# MPC.net
KiCad netlist of a schematic drawn in Altium Designer
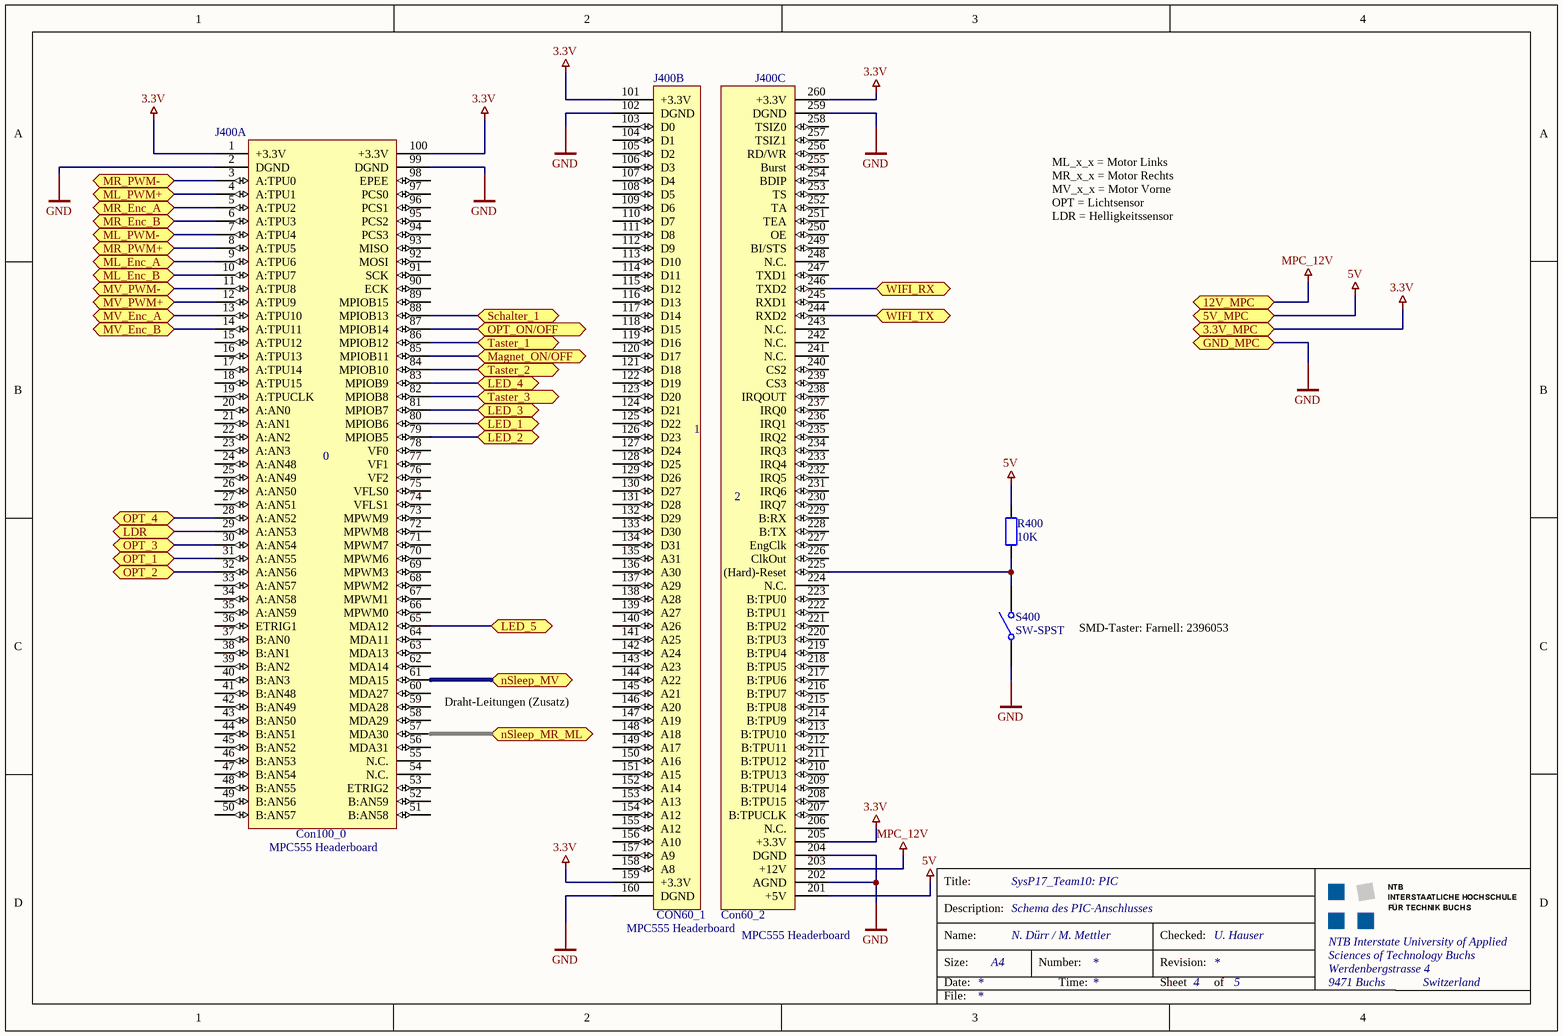
[diagram p0: MPC.SchDoc]

(export (version "E")
  (design (tool "Eeschema 10.0.6"))
  (components
    (comp (ref "J400")
      (value "MPC555 Headerboard")
      (footprint "MPC555 Headerboard THT")
      (description "NTB MPC555 Headerboard")
      (libsource (lib "ch.ntb.inf.altiumlib_2011-02-10") (part "MPC555 Headerboard"))
    )
    (comp (ref "R400")
      (value "10K")
      (footprint "GEN_R0805_H")
      (description "generic resistor")
      (fields
        (field (name "MANUFACTURER") "Tbd")
        (field (name "Comment") "Generic")
        (field (name "PUBLISHER") "Altium Limited")
      )
      (libsource (lib "Motortreiber") (part "GEN_R_2"))
    )
    (comp (ref "S400")
      (value "SW-SPST")
      (footprint "Taster")
      (description "Single-Pole, Single-Throw Switch")
      (fields (field (name "PUBLISHER") "Altium Limited"))
      (libsource (lib "Miscellaneous Devices") (part "SW-SPST"))
    )
  )
  (nets
    (net (code "1") (name "/LDR") (class "Default")
      (node (ref "J400") (pin "29") (pinfunction "A:AN53_29") (pintype "bidirectional"))
    )
    (net (code "2") (name "/LED_1") (class "Default")
      (node (ref "J400") (pin "80") (pinfunction "MPIOB6_80") (pintype "bidirectional"))
    )
    (net (code "3") (name "/LED_2") (class "Default")
      (node (ref "J400") (pin "79") (pinfunction "MPIOB5_79") (pintype "bidirectional"))
    )
    (net (code "4") (name "/LED_3") (class "Default")
      (node (ref "J400") (pin "81") (pinfunction "MPIOB7_81") (pintype "bidirectional"))
    )
    (net (code "5") (name "/LED_4") (class "Default")
      (node (ref "J400") (pin "83") (pinfunction "MPIOB9_83") (pintype "bidirectional"))
    )
    (net (code "6") (name "/LED_5") (class "Default")
      (node (ref "J400") (pin "65") (pinfunction "MDA12_65") (pintype "bidirectional"))
    )
    (net (code "7") (name "/ML_Enc_A") (class "Default")
      (node (ref "J400") (pin "9") (pinfunction "A:TPU6_9") (pintype "bidirectional"))
    )
    (net (code "8") (name "/ML_Enc_B") (class "Default")
      (node (ref "J400") (pin "10") (pinfunction "A:TPU7_10") (pintype "bidirectional"))
    )
    (net (code "9") (name "/ML_PWM+") (class "Default")
      (node (ref "J400") (pin "4") (pinfunction "A:TPU1_4") (pintype "bidirectional"))
    )
    (net (code "10") (name "/ML_PWM-") (class "Default")
      (node (ref "J400") (pin "7") (pinfunction "A:TPU4_7") (pintype "bidirectional"))
    )
    (net (code "11") (name "/MR_Enc_A") (class "Default")
      (node (ref "J400") (pin "5") (pinfunction "A:TPU2_5") (pintype "bidirectional"))
    )
    (net (code "12") (name "/MR_Enc_B") (class "Default")
      (node (ref "J400") (pin "6") (pinfunction "A:TPU3_6") (pintype "bidirectional"))
    )
    (net (code "13") (name "/MR_PWM+") (class "Default")
      (node (ref "J400") (pin "8") (pinfunction "A:TPU5_8") (pintype "bidirectional"))
    )
    (net (code "14") (name "/MR_PWM-") (class "Default")
      (node (ref "J400") (pin "3") (pinfunction "A:TPU0_3") (pintype "bidirectional"))
    )
    (net (code "15") (name "/MV_Enc_A") (class "Default")
      (node (ref "J400") (pin "13") (pinfunction "A:TPU10_13") (pintype "bidirectional"))
    )
    (net (code "16") (name "/MV_Enc_B") (class "Default")
      (node (ref "J400") (pin "14") (pinfunction "A:TPU11_14") (pintype "bidirectional"))
    )
    (net (code "17") (name "/MV_PWM+") (class "Default")
      (node (ref "J400") (pin "12") (pinfunction "A:TPU9_12") (pintype "bidirectional"))
    )
    (net (code "18") (name "/MV_PWM-") (class "Default")
      (node (ref "J400") (pin "11") (pinfunction "A:TPU8_11") (pintype "bidirectional"))
    )
    (net (code "19") (name "/Magnet_ON{slash}OFF") (class "Default")
      (node (ref "J400") (pin "85") (pinfunction "MPIOB11_85") (pintype "bidirectional"))
    )
    (net (code "20") (name "/OPT_1") (class "Default")
      (node (ref "J400") (pin "31") (pinfunction "A:AN55_31") (pintype "bidirectional"))
    )
    (net (code "21") (name "/OPT_2") (class "Default")
      (node (ref "J400") (pin "32") (pinfunction "A:AN56_32") (pintype "bidirectional"))
    )
    (net (code "22") (name "/OPT_3") (class "Default")
      (node (ref "J400") (pin "30") (pinfunction "A:AN54_30") (pintype "bidirectional"))
    )
    (net (code "23") (name "/OPT_4") (class "Default")
      (node (ref "J400") (pin "28") (pinfunction "A:AN52_28") (pintype "bidirectional"))
    )
    (net (code "24") (name "/OPT_ON{slash}OFF") (class "Default")
      (node (ref "J400") (pin "87") (pinfunction "MPIOB14_87") (pintype "bidirectional"))
    )
    (net (code "25") (name "/Schalter_1") (class "Default")
      (node (ref "J400") (pin "88") (pinfunction "MPIOB13_88") (pintype "bidirectional"))
    )
    (net (code "26") (name "/Taster_1") (class "Default")
      (node (ref "J400") (pin "86") (pinfunction "MPIOB12_86") (pintype "bidirectional"))
    )
    (net (code "27") (name "/Taster_2") (class "Default")
      (node (ref "J400") (pin "84") (pinfunction "MPIOB10_84") (pintype "bidirectional"))
    )
    (net (code "28") (name "/Taster_3") (class "Default")
      (node (ref "J400") (pin "82") (pinfunction "MPIOB8_82") (pintype "bidirectional"))
    )
    (net (code "29") (name "/WIFI_RX") (class "Default")
      (node (ref "J400") (pin "246") (pinfunction "TXD2_246") (pintype "bidirectional"))
    )
    (net (code "30") (name "/WIFI_TX") (class "Default")
      (node (ref "J400") (pin "244") (pinfunction "RXD2_244") (pintype "bidirectional"))
    )
    (net (code "31") (name "/nSleep_MR_ML") (class "Default")
      (node (ref "J400") (pin "57") (pinfunction "MDA30_57") (pintype "bidirectional"))
    )
    (net (code "32") (name "/nSleep_MV") (class "Default")
      (node (ref "J400") (pin "61") (pinfunction "MDA15_61") (pintype "bidirectional"))
    )
    (net (code "33") (name "3.3V") (class "Default")
      (node (ref "J400") (pin "1") (pinfunction "+3.3V_1") (pintype "power_in"))
      (node (ref "J400") (pin "100") (pinfunction "+3.3V_100") (pintype "power_in"))
      (node (ref "J400") (pin "101") (pinfunction "+3.3V_101") (pintype "power_in"))
      (node (ref "J400") (pin "159") (pinfunction "+3.3V_159") (pintype "power_in"))
      (node (ref "J400") (pin "205") (pinfunction "+3.3V_205") (pintype "power_in"))
      (node (ref "J400") (pin "260") (pinfunction "+3.3V_260") (pintype "power_in"))
    )
    (net (code "34") (name "5V") (class "Default")
      (node (ref "J400") (pin "201") (pinfunction "+5V_201") (pintype "power_in"))
      (node (ref "R400") (pin "2") (pinfunction "2_2") (pintype "passive"))
    )
    (net (code "35") (name "GND") (class "Default")
      (node (ref "J400") (pin "102") (pinfunction "DGND_102") (pintype "power_in"))
      (node (ref "J400") (pin "160") (pinfunction "DGND_160") (pintype "power_in"))
      (node (ref "J400") (pin "2") (pinfunction "DGND_2") (pintype "power_in"))
      (node (ref "J400") (pin "202") (pinfunction "AGND_202") (pintype "power_in"))
      (node (ref "J400") (pin "204") (pinfunction "DGND_204") (pintype "power_in"))
      (node (ref "J400") (pin "259") (pinfunction "DGND_259") (pintype "power_in"))
      (node (ref "J400") (pin "99") (pinfunction "DGND_99") (pintype "power_in"))
      (node (ref "S400") (pin "1") (pinfunction "COMMON_1") (pintype "passive"))
    )
    (net (code "36") (name "MPC_12V") (class "Default")
      (node (ref "J400") (pin "203") (pinfunction "+12V_203") (pintype "power_in"))
    )
    (net (code "37") (name "Net-(J400C-(Hard)-Reset)") (class "Default")
      (node (ref "J400") (pin "225") (pinfunction "(Hard)-Reset_225") (pintype "bidirectional"))
      (node (ref "R400") (pin "1") (pinfunction "1_1") (pintype "passive"))
      (node (ref "S400") (pin "0") (pinfunction "NO_0") (pintype "passive"))
    )
    (net (code "38") (name "unconnected-(J400A-A:AN0-Pad20)") (class "Default")
      (node (ref "J400") (pin "20") (pinfunction "A:AN0_20") (pintype "bidirectional"))
    )
    (net (code "39") (name "unconnected-(J400A-A:AN1-Pad21)") (class "Default")
      (node (ref "J400") (pin "21") (pinfunction "A:AN1_21") (pintype "bidirectional"))
    )
    (net (code "40") (name "unconnected-(J400A-A:AN2-Pad22)") (class "Default")
      (node (ref "J400") (pin "22") (pinfunction "A:AN2_22") (pintype "bidirectional"))
    )
    (net (code "41") (name "unconnected-(J400A-A:AN3-Pad23)") (class "Default")
      (node (ref "J400") (pin "23") (pinfunction "A:AN3_23") (pintype "bidirectional"))
    )
    (net (code "42") (name "unconnected-(J400A-A:AN48-Pad24)") (class "Default")
      (node (ref "J400") (pin "24") (pinfunction "A:AN48_24") (pintype "bidirectional"))
    )
    (net (code "43") (name "unconnected-(J400A-A:AN49-Pad25)") (class "Default")
      (node (ref "J400") (pin "25") (pinfunction "A:AN49_25") (pintype "bidirectional"))
    )
    (net (code "44") (name "unconnected-(J400A-A:AN50-Pad26)") (class "Default")
      (node (ref "J400") (pin "26") (pinfunction "A:AN50_26") (pintype "bidirectional"))
    )
    (net (code "45") (name "unconnected-(J400A-A:AN51-Pad27)") (class "Default")
      (node (ref "J400") (pin "27") (pinfunction "A:AN51_27") (pintype "bidirectional"))
    )
    (net (code "46") (name "unconnected-(J400A-A:AN57-Pad33)") (class "Default")
      (node (ref "J400") (pin "33") (pinfunction "A:AN57_33") (pintype "bidirectional"))
    )
    (net (code "47") (name "unconnected-(J400A-A:AN58-Pad34)") (class "Default")
      (node (ref "J400") (pin "34") (pinfunction "A:AN58_34") (pintype "bidirectional"))
    )
    (net (code "48") (name "unconnected-(J400A-A:AN59-Pad35)") (class "Default")
      (node (ref "J400") (pin "35") (pinfunction "A:AN59_35") (pintype "bidirectional"))
    )
    (net (code "49") (name "unconnected-(J400A-A:TPU12-Pad15)") (class "Default")
      (node (ref "J400") (pin "15") (pinfunction "A:TPU12_15") (pintype "bidirectional"))
    )
    (net (code "50") (name "unconnected-(J400A-A:TPU13-Pad16)") (class "Default")
      (node (ref "J400") (pin "16") (pinfunction "A:TPU13_16") (pintype "bidirectional"))
    )
    (net (code "51") (name "unconnected-(J400A-A:TPU14-Pad17)") (class "Default")
      (node (ref "J400") (pin "17") (pinfunction "A:TPU14_17") (pintype "bidirectional"))
    )
    (net (code "52") (name "unconnected-(J400A-A:TPU15-Pad18)") (class "Default")
      (node (ref "J400") (pin "18") (pinfunction "A:TPU15_18") (pintype "bidirectional"))
    )
    (net (code "53") (name "unconnected-(J400A-A:TPUCLK-Pad19)") (class "Default")
      (node (ref "J400") (pin "19") (pinfunction "A:TPUCLK_19") (pintype "bidirectional"))
    )
    (net (code "54") (name "unconnected-(J400A-B:AN0-Pad37)") (class "Default")
      (node (ref "J400") (pin "37") (pinfunction "B:AN0_37") (pintype "bidirectional"))
    )
    (net (code "55") (name "unconnected-(J400A-B:AN1-Pad38)") (class "Default")
      (node (ref "J400") (pin "38") (pinfunction "B:AN1_38") (pintype "bidirectional"))
    )
    (net (code "56") (name "unconnected-(J400A-B:AN2-Pad39)") (class "Default")
      (node (ref "J400") (pin "39") (pinfunction "B:AN2_39") (pintype "bidirectional"))
    )
    (net (code "57") (name "unconnected-(J400A-B:AN3-Pad40)") (class "Default")
      (node (ref "J400") (pin "40") (pinfunction "B:AN3_40") (pintype "bidirectional"))
    )
    (net (code "58") (name "unconnected-(J400A-B:AN48-Pad41)") (class "Default")
      (node (ref "J400") (pin "41") (pinfunction "B:AN48_41") (pintype "bidirectional"))
    )
    (net (code "59") (name "unconnected-(J400A-B:AN49-Pad42)") (class "Default")
      (node (ref "J400") (pin "42") (pinfunction "B:AN49_42") (pintype "bidirectional"))
    )
    (net (code "60") (name "unconnected-(J400A-B:AN50-Pad43)") (class "Default")
      (node (ref "J400") (pin "43") (pinfunction "B:AN50_43") (pintype "bidirectional"))
    )
    (net (code "61") (name "unconnected-(J400A-B:AN51-Pad44)") (class "Default")
      (node (ref "J400") (pin "44") (pinfunction "B:AN51_44") (pintype "bidirectional"))
    )
    (net (code "62") (name "unconnected-(J400A-B:AN52-Pad45)") (class "Default")
      (node (ref "J400") (pin "45") (pinfunction "B:AN52_45") (pintype "bidirectional"))
    )
    (net (code "63") (name "unconnected-(J400A-B:AN53-Pad46)") (class "Default")
      (node (ref "J400") (pin "46") (pinfunction "B:AN53_46") (pintype "bidirectional"))
    )
    (net (code "64") (name "unconnected-(J400A-B:AN54-Pad47)") (class "Default")
      (node (ref "J400") (pin "47") (pinfunction "B:AN54_47") (pintype "bidirectional"))
    )
    (net (code "65") (name "unconnected-(J400A-B:AN55-Pad48)") (class "Default")
      (node (ref "J400") (pin "48") (pinfunction "B:AN55_48") (pintype "bidirectional"))
    )
    (net (code "66") (name "unconnected-(J400A-B:AN56-Pad49)") (class "Default")
      (node (ref "J400") (pin "49") (pinfunction "B:AN56_49") (pintype "bidirectional"))
    )
    (net (code "67") (name "unconnected-(J400A-B:AN57-Pad50)") (class "Default")
      (node (ref "J400") (pin "50") (pinfunction "B:AN57_50") (pintype "bidirectional"))
    )
    (net (code "68") (name "unconnected-(J400A-B:AN58-Pad51)") (class "Default")
      (node (ref "J400") (pin "51") (pinfunction "B:AN58_51") (pintype "bidirectional"))
    )
    (net (code "69") (name "unconnected-(J400A-B:AN59-Pad52)") (class "Default")
      (node (ref "J400") (pin "52") (pinfunction "B:AN59_52") (pintype "bidirectional"))
    )
    (net (code "70") (name "unconnected-(J400A-ECK-Pad90)") (class "Default")
      (node (ref "J400") (pin "90") (pinfunction "ECK_90") (pintype "bidirectional"))
    )
    (net (code "71") (name "unconnected-(J400A-EPEE-Pad98)") (class "Default")
      (node (ref "J400") (pin "98") (pinfunction "EPEE_98") (pintype "bidirectional"))
    )
    (net (code "72") (name "unconnected-(J400A-ETRIG1-Pad36)") (class "Default")
      (node (ref "J400") (pin "36") (pinfunction "ETRIG1_36") (pintype "bidirectional"))
    )
    (net (code "73") (name "unconnected-(J400A-ETRIG2-Pad53)") (class "Default")
      (node (ref "J400") (pin "53") (pinfunction "ETRIG2_53") (pintype "bidirectional"))
    )
    (net (code "74") (name "unconnected-(J400A-MDA11-Pad64)") (class "Default")
      (node (ref "J400") (pin "64") (pinfunction "MDA11_64") (pintype "bidirectional"))
    )
    (net (code "75") (name "unconnected-(J400A-MDA13-Pad63)") (class "Default")
      (node (ref "J400") (pin "63") (pinfunction "MDA13_63") (pintype "bidirectional"))
    )
    (net (code "76") (name "unconnected-(J400A-MDA14-Pad62)") (class "Default")
      (node (ref "J400") (pin "62") (pinfunction "MDA14_62") (pintype "bidirectional"))
    )
    (net (code "77") (name "unconnected-(J400A-MDA27-Pad60)") (class "Default")
      (node (ref "J400") (pin "60") (pinfunction "MDA27_60") (pintype "bidirectional"))
    )
    (net (code "78") (name "unconnected-(J400A-MDA28-Pad59)") (class "Default")
      (node (ref "J400") (pin "59") (pinfunction "MDA28_59") (pintype "bidirectional"))
    )
    (net (code "79") (name "unconnected-(J400A-MDA29-Pad58)") (class "Default")
      (node (ref "J400") (pin "58") (pinfunction "MDA29_58") (pintype "bidirectional"))
    )
    (net (code "80") (name "unconnected-(J400A-MDA31-Pad56)") (class "Default")
      (node (ref "J400") (pin "56") (pinfunction "MDA31_56") (pintype "bidirectional"))
    )
    (net (code "81") (name "unconnected-(J400A-MISO-Pad93)") (class "Default")
      (node (ref "J400") (pin "93") (pinfunction "MISO_93") (pintype "bidirectional"))
    )
    (net (code "82") (name "unconnected-(J400A-MOSI-Pad92)") (class "Default")
      (node (ref "J400") (pin "92") (pinfunction "MOSI_92") (pintype "bidirectional"))
    )
    (net (code "83") (name "unconnected-(J400A-MPIOB15-Pad89)") (class "Default")
      (node (ref "J400") (pin "89") (pinfunction "MPIOB15_89") (pintype "bidirectional"))
    )
    (net (code "84") (name "unconnected-(J400A-MPWM0-Pad66)") (class "Default")
      (node (ref "J400") (pin "66") (pinfunction "MPWM0_66") (pintype "bidirectional"))
    )
    (net (code "85") (name "unconnected-(J400A-MPWM1-Pad67)") (class "Default")
      (node (ref "J400") (pin "67") (pinfunction "MPWM1_67") (pintype "bidirectional"))
    )
    (net (code "86") (name "unconnected-(J400A-MPWM2-Pad68)") (class "Default")
      (node (ref "J400") (pin "68") (pinfunction "MPWM2_68") (pintype "bidirectional"))
    )
    (net (code "87") (name "unconnected-(J400A-MPWM3-Pad69)") (class "Default")
      (node (ref "J400") (pin "69") (pinfunction "MPWM3_69") (pintype "bidirectional"))
    )
    (net (code "88") (name "unconnected-(J400A-MPWM6-Pad70)") (class "Default")
      (node (ref "J400") (pin "70") (pinfunction "MPWM6_70") (pintype "bidirectional"))
    )
    (net (code "89") (name "unconnected-(J400A-MPWM7-Pad71)") (class "Default")
      (node (ref "J400") (pin "71") (pinfunction "MPWM7_71") (pintype "bidirectional"))
    )
    (net (code "90") (name "unconnected-(J400A-MPWM8-Pad72)") (class "Default")
      (node (ref "J400") (pin "72") (pinfunction "MPWM8_72") (pintype "bidirectional"))
    )
    (net (code "91") (name "unconnected-(J400A-MPWM9-Pad73)") (class "Default")
      (node (ref "J400") (pin "73") (pinfunction "MPWM9_73") (pintype "bidirectional"))
    )
    (net (code "92") (name "unconnected-(J400A-N.C.-Pad54)") (class "Default")
      (node (ref "J400") (pin "54") (pinfunction "N.C._54") (pintype "tri_state"))
    )
    (net (code "93") (name "unconnected-(J400A-N.C.-Pad55)") (class "Default")
      (node (ref "J400") (pin "55") (pinfunction "N.C._55") (pintype "tri_state"))
    )
    (net (code "94") (name "unconnected-(J400A-PCS0-Pad97)") (class "Default")
      (node (ref "J400") (pin "97") (pinfunction "PCS0_97") (pintype "bidirectional"))
    )
    (net (code "95") (name "unconnected-(J400A-PCS1-Pad96)") (class "Default")
      (node (ref "J400") (pin "96") (pinfunction "PCS1_96") (pintype "bidirectional"))
    )
    (net (code "96") (name "unconnected-(J400A-PCS2-Pad95)") (class "Default")
      (node (ref "J400") (pin "95") (pinfunction "PCS2_95") (pintype "bidirectional"))
    )
    (net (code "97") (name "unconnected-(J400A-PCS3-Pad94)") (class "Default")
      (node (ref "J400") (pin "94") (pinfunction "PCS3_94") (pintype "bidirectional"))
    )
    (net (code "98") (name "unconnected-(J400A-SCK-Pad91)") (class "Default")
      (node (ref "J400") (pin "91") (pinfunction "SCK_91") (pintype "bidirectional"))
    )
    (net (code "99") (name "unconnected-(J400A-VF0-Pad78)") (class "Default")
      (node (ref "J400") (pin "78") (pinfunction "VF0_78") (pintype "bidirectional"))
    )
    (net (code "100") (name "unconnected-(J400A-VF1-Pad77)") (class "Default")
      (node (ref "J400") (pin "77") (pinfunction "VF1_77") (pintype "bidirectional"))
    )
    (net (code "101") (name "unconnected-(J400A-VF2-Pad76)") (class "Default")
      (node (ref "J400") (pin "76") (pinfunction "VF2_76") (pintype "bidirectional"))
    )
    (net (code "102") (name "unconnected-(J400A-VFLS0-Pad75)") (class "Default")
      (node (ref "J400") (pin "75") (pinfunction "VFLS0_75") (pintype "bidirectional"))
    )
    (net (code "103") (name "unconnected-(J400A-VFLS1-Pad74)") (class "Default")
      (node (ref "J400") (pin "74") (pinfunction "VFLS1_74") (pintype "bidirectional"))
    )
    (net (code "104") (name "unconnected-(J400B-A8-Pad158)") (class "Default")
      (node (ref "J400") (pin "158") (pinfunction "A8_158") (pintype "bidirectional"))
    )
    (net (code "105") (name "unconnected-(J400B-A9-Pad157)") (class "Default")
      (node (ref "J400") (pin "157") (pinfunction "A9_157") (pintype "bidirectional"))
    )
    (net (code "106") (name "unconnected-(J400B-A10-Pad156)") (class "Default")
      (node (ref "J400") (pin "156") (pinfunction "A10_156") (pintype "bidirectional"))
    )
    (net (code "107") (name "unconnected-(J400B-A12-Pad154)") (class "Default")
      (node (ref "J400") (pin "154") (pinfunction "A12_154") (pintype "bidirectional"))
    )
    (net (code "108") (name "unconnected-(J400B-A12-Pad155)") (class "Default")
      (node (ref "J400") (pin "155") (pinfunction "A12_155") (pintype "bidirectional"))
    )
    (net (code "109") (name "unconnected-(J400B-A13-Pad153)") (class "Default")
      (node (ref "J400") (pin "153") (pinfunction "A13_153") (pintype "bidirectional"))
    )
    (net (code "110") (name "unconnected-(J400B-A14-Pad152)") (class "Default")
      (node (ref "J400") (pin "152") (pinfunction "A14_152") (pintype "bidirectional"))
    )
    (net (code "111") (name "unconnected-(J400B-A15-Pad151)") (class "Default")
      (node (ref "J400") (pin "151") (pinfunction "A15_151") (pintype "bidirectional"))
    )
    (net (code "112") (name "unconnected-(J400B-A16-Pad150)") (class "Default")
      (node (ref "J400") (pin "150") (pinfunction "A16_150") (pintype "bidirectional"))
    )
    (net (code "113") (name "unconnected-(J400B-A17-Pad149)") (class "Default")
      (node (ref "J400") (pin "149") (pinfunction "A17_149") (pintype "bidirectional"))
    )
    (net (code "114") (name "unconnected-(J400B-A18-Pad148)") (class "Default")
      (node (ref "J400") (pin "148") (pinfunction "A18_148") (pintype "bidirectional"))
    )
    (net (code "115") (name "unconnected-(J400B-A19-Pad147)") (class "Default")
      (node (ref "J400") (pin "147") (pinfunction "A19_147") (pintype "bidirectional"))
    )
    (net (code "116") (name "unconnected-(J400B-A20-Pad146)") (class "Default")
      (node (ref "J400") (pin "146") (pinfunction "A20_146") (pintype "bidirectional"))
    )
    (net (code "117") (name "unconnected-(J400B-A21-Pad145)") (class "Default")
      (node (ref "J400") (pin "145") (pinfunction "A21_145") (pintype "bidirectional"))
    )
    (net (code "118") (name "unconnected-(J400B-A22-Pad144)") (class "Default")
      (node (ref "J400") (pin "144") (pinfunction "A22_144") (pintype "bidirectional"))
    )
    (net (code "119") (name "unconnected-(J400B-A23-Pad143)") (class "Default")
      (node (ref "J400") (pin "143") (pinfunction "A23_143") (pintype "bidirectional"))
    )
    (net (code "120") (name "unconnected-(J400B-A24-Pad142)") (class "Default")
      (node (ref "J400") (pin "142") (pinfunction "A24_142") (pintype "bidirectional"))
    )
    (net (code "121") (name "unconnected-(J400B-A25-Pad141)") (class "Default")
      (node (ref "J400") (pin "141") (pinfunction "A25_141") (pintype "bidirectional"))
    )
    (net (code "122") (name "unconnected-(J400B-A26-Pad140)") (class "Default")
      (node (ref "J400") (pin "140") (pinfunction "A26_140") (pintype "bidirectional"))
    )
    (net (code "123") (name "unconnected-(J400B-A27-Pad139)") (class "Default")
      (node (ref "J400") (pin "139") (pinfunction "A27_139") (pintype "bidirectional"))
    )
    (net (code "124") (name "unconnected-(J400B-A28-Pad138)") (class "Default")
      (node (ref "J400") (pin "138") (pinfunction "A28_138") (pintype "bidirectional"))
    )
    (net (code "125") (name "unconnected-(J400B-A29-Pad137)") (class "Default")
      (node (ref "J400") (pin "137") (pinfunction "A29_137") (pintype "bidirectional"))
    )
    (net (code "126") (name "unconnected-(J400B-A30-Pad136)") (class "Default")
      (node (ref "J400") (pin "136") (pinfunction "A30_136") (pintype "bidirectional"))
    )
    (net (code "127") (name "unconnected-(J400B-A31-Pad135)") (class "Default")
      (node (ref "J400") (pin "135") (pinfunction "A31_135") (pintype "bidirectional"))
    )
    (net (code "128") (name "unconnected-(J400B-D0-Pad103)") (class "Default")
      (node (ref "J400") (pin "103") (pinfunction "D0_103") (pintype "bidirectional"))
    )
    (net (code "129") (name "unconnected-(J400B-D1-Pad104)") (class "Default")
      (node (ref "J400") (pin "104") (pinfunction "D1_104") (pintype "bidirectional"))
    )
    (net (code "130") (name "unconnected-(J400B-D2-Pad105)") (class "Default")
      (node (ref "J400") (pin "105") (pinfunction "D2_105") (pintype "bidirectional"))
    )
    (net (code "131") (name "unconnected-(J400B-D3-Pad106)") (class "Default")
      (node (ref "J400") (pin "106") (pinfunction "D3_106") (pintype "bidirectional"))
    )
    (net (code "132") (name "unconnected-(J400B-D4-Pad107)") (class "Default")
      (node (ref "J400") (pin "107") (pinfunction "D4_107") (pintype "bidirectional"))
    )
    (net (code "133") (name "unconnected-(J400B-D5-Pad108)") (class "Default")
      (node (ref "J400") (pin "108") (pinfunction "D5_108") (pintype "bidirectional"))
    )
    (net (code "134") (name "unconnected-(J400B-D6-Pad109)") (class "Default")
      (node (ref "J400") (pin "109") (pinfunction "D6_109") (pintype "bidirectional"))
    )
    (net (code "135") (name "unconnected-(J400B-D7-Pad110)") (class "Default")
      (node (ref "J400") (pin "110") (pinfunction "D7_110") (pintype "bidirectional"))
    )
    (net (code "136") (name "unconnected-(J400B-D8-Pad111)") (class "Default")
      (node (ref "J400") (pin "111") (pinfunction "D8_111") (pintype "bidirectional"))
    )
    (net (code "137") (name "unconnected-(J400B-D9-Pad112)") (class "Default")
      (node (ref "J400") (pin "112") (pinfunction "D9_112") (pintype "bidirectional"))
    )
    (net (code "138") (name "unconnected-(J400B-D10-Pad113)") (class "Default")
      (node (ref "J400") (pin "113") (pinfunction "D10_113") (pintype "bidirectional"))
    )
    (net (code "139") (name "unconnected-(J400B-D11-Pad114)") (class "Default")
      (node (ref "J400") (pin "114") (pinfunction "D11_114") (pintype "bidirectional"))
    )
    (net (code "140") (name "unconnected-(J400B-D12-Pad115)") (class "Default")
      (node (ref "J400") (pin "115") (pinfunction "D12_115") (pintype "bidirectional"))
    )
    (net (code "141") (name "unconnected-(J400B-D13-Pad116)") (class "Default")
      (node (ref "J400") (pin "116") (pinfunction "D13_116") (pintype "bidirectional"))
    )
    (net (code "142") (name "unconnected-(J400B-D14-Pad117)") (class "Default")
      (node (ref "J400") (pin "117") (pinfunction "D14_117") (pintype "bidirectional"))
    )
    (net (code "143") (name "unconnected-(J400B-D15-Pad118)") (class "Default")
      (node (ref "J400") (pin "118") (pinfunction "D15_118") (pintype "bidirectional"))
    )
    (net (code "144") (name "unconnected-(J400B-D16-Pad119)") (class "Default")
      (node (ref "J400") (pin "119") (pinfunction "D16_119") (pintype "bidirectional"))
    )
    (net (code "145") (name "unconnected-(J400B-D17-Pad120)") (class "Default")
      (node (ref "J400") (pin "120") (pinfunction "D17_120") (pintype "bidirectional"))
    )
    (net (code "146") (name "unconnected-(J400B-D18-Pad121)") (class "Default")
      (node (ref "J400") (pin "121") (pinfunction "D18_121") (pintype "bidirectional"))
    )
    (net (code "147") (name "unconnected-(J400B-D19-Pad122)") (class "Default")
      (node (ref "J400") (pin "122") (pinfunction "D19_122") (pintype "bidirectional"))
    )
    (net (code "148") (name "unconnected-(J400B-D20-Pad123)") (class "Default")
      (node (ref "J400") (pin "123") (pinfunction "D20_123") (pintype "bidirectional"))
    )
    (net (code "149") (name "unconnected-(J400B-D21-Pad124)") (class "Default")
      (node (ref "J400") (pin "124") (pinfunction "D21_124") (pintype "bidirectional"))
    )
    (net (code "150") (name "unconnected-(J400B-D22-Pad125)") (class "Default")
      (node (ref "J400") (pin "125") (pinfunction "D22_125") (pintype "bidirectional"))
    )
    (net (code "151") (name "unconnected-(J400B-D23-Pad126)") (class "Default")
      (node (ref "J400") (pin "126") (pinfunction "D23_126") (pintype "bidirectional"))
    )
    (net (code "152") (name "unconnected-(J400B-D24-Pad127)") (class "Default")
      (node (ref "J400") (pin "127") (pinfunction "D24_127") (pintype "bidirectional"))
    )
    (net (code "153") (name "unconnected-(J400B-D25-Pad128)") (class "Default")
      (node (ref "J400") (pin "128") (pinfunction "D25_128") (pintype "bidirectional"))
    )
    (net (code "154") (name "unconnected-(J400B-D26-Pad129)") (class "Default")
      (node (ref "J400") (pin "129") (pinfunction "D26_129") (pintype "bidirectional"))
    )
    (net (code "155") (name "unconnected-(J400B-D27-Pad130)") (class "Default")
      (node (ref "J400") (pin "130") (pinfunction "D27_130") (pintype "bidirectional"))
    )
    (net (code "156") (name "unconnected-(J400B-D28-Pad131)") (class "Default")
      (node (ref "J400") (pin "131") (pinfunction "D28_131") (pintype "bidirectional"))
    )
    (net (code "157") (name "unconnected-(J400B-D29-Pad132)") (class "Default")
      (node (ref "J400") (pin "132") (pinfunction "D29_132") (pintype "bidirectional"))
    )
    (net (code "158") (name "unconnected-(J400B-D30-Pad133)") (class "Default")
      (node (ref "J400") (pin "133") (pinfunction "D30_133") (pintype "bidirectional"))
    )
    (net (code "159") (name "unconnected-(J400B-D31-Pad134)") (class "Default")
      (node (ref "J400") (pin "134") (pinfunction "D31_134") (pintype "bidirectional"))
    )
    (net (code "160") (name "unconnected-(J400C-B:RX-Pad229)") (class "Default")
      (node (ref "J400") (pin "229") (pinfunction "B:RX_229") (pintype "bidirectional"))
    )
    (net (code "161") (name "unconnected-(J400C-B:TPU0-Pad223)") (class "Default")
      (node (ref "J400") (pin "223") (pinfunction "B:TPU0_223") (pintype "bidirectional"))
    )
    (net (code "162") (name "unconnected-(J400C-B:TPU1-Pad222)") (class "Default")
      (node (ref "J400") (pin "222") (pinfunction "B:TPU1_222") (pintype "bidirectional"))
    )
    (net (code "163") (name "unconnected-(J400C-B:TPU2-Pad221)") (class "Default")
      (node (ref "J400") (pin "221") (pinfunction "B:TPU2_221") (pintype "bidirectional"))
    )
    (net (code "164") (name "unconnected-(J400C-B:TPU3-Pad220)") (class "Default")
      (node (ref "J400") (pin "220") (pinfunction "B:TPU3_220") (pintype "bidirectional"))
    )
    (net (code "165") (name "unconnected-(J400C-B:TPU4-Pad219)") (class "Default")
      (node (ref "J400") (pin "219") (pinfunction "B:TPU4_219") (pintype "bidirectional"))
    )
    (net (code "166") (name "unconnected-(J400C-B:TPU5-Pad218)") (class "Default")
      (node (ref "J400") (pin "218") (pinfunction "B:TPU5_218") (pintype "bidirectional"))
    )
    (net (code "167") (name "unconnected-(J400C-B:TPU6-Pad217)") (class "Default")
      (node (ref "J400") (pin "217") (pinfunction "B:TPU6_217") (pintype "bidirectional"))
    )
    (net (code "168") (name "unconnected-(J400C-B:TPU7-Pad216)") (class "Default")
      (node (ref "J400") (pin "216") (pinfunction "B:TPU7_216") (pintype "bidirectional"))
    )
    (net (code "169") (name "unconnected-(J400C-B:TPU8-Pad215)") (class "Default")
      (node (ref "J400") (pin "215") (pinfunction "B:TPU8_215") (pintype "bidirectional"))
    )
    (net (code "170") (name "unconnected-(J400C-B:TPU9-Pad214)") (class "Default")
      (node (ref "J400") (pin "214") (pinfunction "B:TPU9_214") (pintype "bidirectional"))
    )
    (net (code "171") (name "unconnected-(J400C-B:TPU10-Pad213)") (class "Default")
      (node (ref "J400") (pin "213") (pinfunction "B:TPU10_213") (pintype "bidirectional"))
    )
    (net (code "172") (name "unconnected-(J400C-B:TPU11-Pad212)") (class "Default")
      (node (ref "J400") (pin "212") (pinfunction "B:TPU11_212") (pintype "bidirectional"))
    )
    (net (code "173") (name "unconnected-(J400C-B:TPU12-Pad211)") (class "Default")
      (node (ref "J400") (pin "211") (pinfunction "B:TPU12_211") (pintype "bidirectional"))
    )
    (net (code "174") (name "unconnected-(J400C-B:TPU13-Pad210)") (class "Default")
      (node (ref "J400") (pin "210") (pinfunction "B:TPU13_210") (pintype "bidirectional"))
    )
    (net (code "175") (name "unconnected-(J400C-B:TPU14-Pad209)") (class "Default")
      (node (ref "J400") (pin "209") (pinfunction "B:TPU14_209") (pintype "bidirectional"))
    )
    (net (code "176") (name "unconnected-(J400C-B:TPU15-Pad208)") (class "Default")
      (node (ref "J400") (pin "208") (pinfunction "B:TPU15_208") (pintype "bidirectional"))
    )
    (net (code "177") (name "unconnected-(J400C-B:TPUCLK-Pad207)") (class "Default")
      (node (ref "J400") (pin "207") (pinfunction "B:TPUCLK_207") (pintype "bidirectional"))
    )
    (net (code "178") (name "unconnected-(J400C-B:TX-Pad228)") (class "Default")
      (node (ref "J400") (pin "228") (pinfunction "B:TX_228") (pintype "bidirectional"))
    )
    (net (code "179") (name "unconnected-(J400C-BDIP-Pad254)") (class "Default")
      (node (ref "J400") (pin "254") (pinfunction "BDIP_254") (pintype "bidirectional"))
    )
    (net (code "180") (name "unconnected-(J400C-BI{slash}STS-Pad249)") (class "Default")
      (node (ref "J400") (pin "249") (pinfunction "BI/STS_249") (pintype "bidirectional"))
    )
    (net (code "181") (name "unconnected-(J400C-Burst-Pad255)") (class "Default")
      (node (ref "J400") (pin "255") (pinfunction "Burst_255") (pintype "bidirectional"))
    )
    (net (code "182") (name "unconnected-(J400C-CS2-Pad240)") (class "Default")
      (node (ref "J400") (pin "240") (pinfunction "CS2_240") (pintype "bidirectional"))
    )
    (net (code "183") (name "unconnected-(J400C-CS3-Pad239)") (class "Default")
      (node (ref "J400") (pin "239") (pinfunction "CS3_239") (pintype "bidirectional"))
    )
    (net (code "184") (name "unconnected-(J400C-ClkOut-Pad226)") (class "Default")
      (node (ref "J400") (pin "226") (pinfunction "ClkOut_226") (pintype "bidirectional"))
    )
    (net (code "185") (name "unconnected-(J400C-EngClk-Pad227)") (class "Default")
      (node (ref "J400") (pin "227") (pinfunction "EngClk_227") (pintype "bidirectional"))
    )
    (net (code "186") (name "unconnected-(J400C-IRQ0-Pad237)") (class "Default")
      (node (ref "J400") (pin "237") (pinfunction "IRQ0_237") (pintype "bidirectional"))
    )
    (net (code "187") (name "unconnected-(J400C-IRQ1-Pad236)") (class "Default")
      (node (ref "J400") (pin "236") (pinfunction "IRQ1_236") (pintype "bidirectional"))
    )
    (net (code "188") (name "unconnected-(J400C-IRQ2-Pad235)") (class "Default")
      (node (ref "J400") (pin "235") (pinfunction "IRQ2_235") (pintype "bidirectional"))
    )
    (net (code "189") (name "unconnected-(J400C-IRQ3-Pad234)") (class "Default")
      (node (ref "J400") (pin "234") (pinfunction "IRQ3_234") (pintype "bidirectional"))
    )
    (net (code "190") (name "unconnected-(J400C-IRQ4-Pad233)") (class "Default")
      (node (ref "J400") (pin "233") (pinfunction "IRQ4_233") (pintype "bidirectional"))
    )
    (net (code "191") (name "unconnected-(J400C-IRQ5-Pad232)") (class "Default")
      (node (ref "J400") (pin "232") (pinfunction "IRQ5_232") (pintype "bidirectional"))
    )
    (net (code "192") (name "unconnected-(J400C-IRQ6-Pad231)") (class "Default")
      (node (ref "J400") (pin "231") (pinfunction "IRQ6_231") (pintype "bidirectional"))
    )
    (net (code "193") (name "unconnected-(J400C-IRQ7-Pad230)") (class "Default")
      (node (ref "J400") (pin "230") (pinfunction "IRQ7_230") (pintype "bidirectional"))
    )
    (net (code "194") (name "unconnected-(J400C-IRQOUT-Pad238)") (class "Default")
      (node (ref "J400") (pin "238") (pinfunction "IRQOUT_238") (pintype "bidirectional"))
    )
    (net (code "195") (name "unconnected-(J400C-N.C.-Pad206)") (class "Default")
      (node (ref "J400") (pin "206") (pinfunction "N.C._206") (pintype "tri_state"))
    )
    (net (code "196") (name "unconnected-(J400C-N.C.-Pad224)") (class "Default")
      (node (ref "J400") (pin "224") (pinfunction "N.C._224") (pintype "tri_state"))
    )
    (net (code "197") (name "unconnected-(J400C-N.C.-Pad241)") (class "Default")
      (node (ref "J400") (pin "241") (pinfunction "N.C._241") (pintype "tri_state"))
    )
    (net (code "198") (name "unconnected-(J400C-N.C.-Pad242)") (class "Default")
      (node (ref "J400") (pin "242") (pinfunction "N.C._242") (pintype "tri_state"))
    )
    (net (code "199") (name "unconnected-(J400C-N.C.-Pad243)") (class "Default")
      (node (ref "J400") (pin "243") (pinfunction "N.C._243") (pintype "tri_state"))
    )
    (net (code "200") (name "unconnected-(J400C-N.C.-Pad248)") (class "Default")
      (node (ref "J400") (pin "248") (pinfunction "N.C._248") (pintype "tri_state"))
    )
    (net (code "201") (name "unconnected-(J400C-OE-Pad250)") (class "Default")
      (node (ref "J400") (pin "250") (pinfunction "OE_250") (pintype "bidirectional"))
    )
    (net (code "202") (name "unconnected-(J400C-RD{slash}WR-Pad256)") (class "Default")
      (node (ref "J400") (pin "256") (pinfunction "RD/WR_256") (pintype "bidirectional"))
    )
    (net (code "203") (name "unconnected-(J400C-RXD1-Pad245)") (class "Default")
      (node (ref "J400") (pin "245") (pinfunction "RXD1_245") (pintype "bidirectional"))
    )
    (net (code "204") (name "unconnected-(J400C-TA-Pad252)") (class "Default")
      (node (ref "J400") (pin "252") (pinfunction "TA_252") (pintype "bidirectional"))
    )
    (net (code "205") (name "unconnected-(J400C-TEA-Pad251)") (class "Default")
      (node (ref "J400") (pin "251") (pinfunction "TEA_251") (pintype "bidirectional"))
    )
    (net (code "206") (name "unconnected-(J400C-TS-Pad253)") (class "Default")
      (node (ref "J400") (pin "253") (pinfunction "TS_253") (pintype "bidirectional"))
    )
    (net (code "207") (name "unconnected-(J400C-TSIZ0-Pad258)") (class "Default")
      (node (ref "J400") (pin "258") (pinfunction "TSIZ0_258") (pintype "bidirectional"))
    )
    (net (code "208") (name "unconnected-(J400C-TSIZ1-Pad257)") (class "Default")
      (node (ref "J400") (pin "257") (pinfunction "TSIZ1_257") (pintype "bidirectional"))
    )
    (net (code "209") (name "unconnected-(J400C-TXD1-Pad247)") (class "Default")
      (node (ref "J400") (pin "247") (pinfunction "TXD1_247") (pintype "bidirectional"))
    )
  )
)
